# BLDC_driver_board.net
KiCad netlist of a schematic drawn in EAGLE
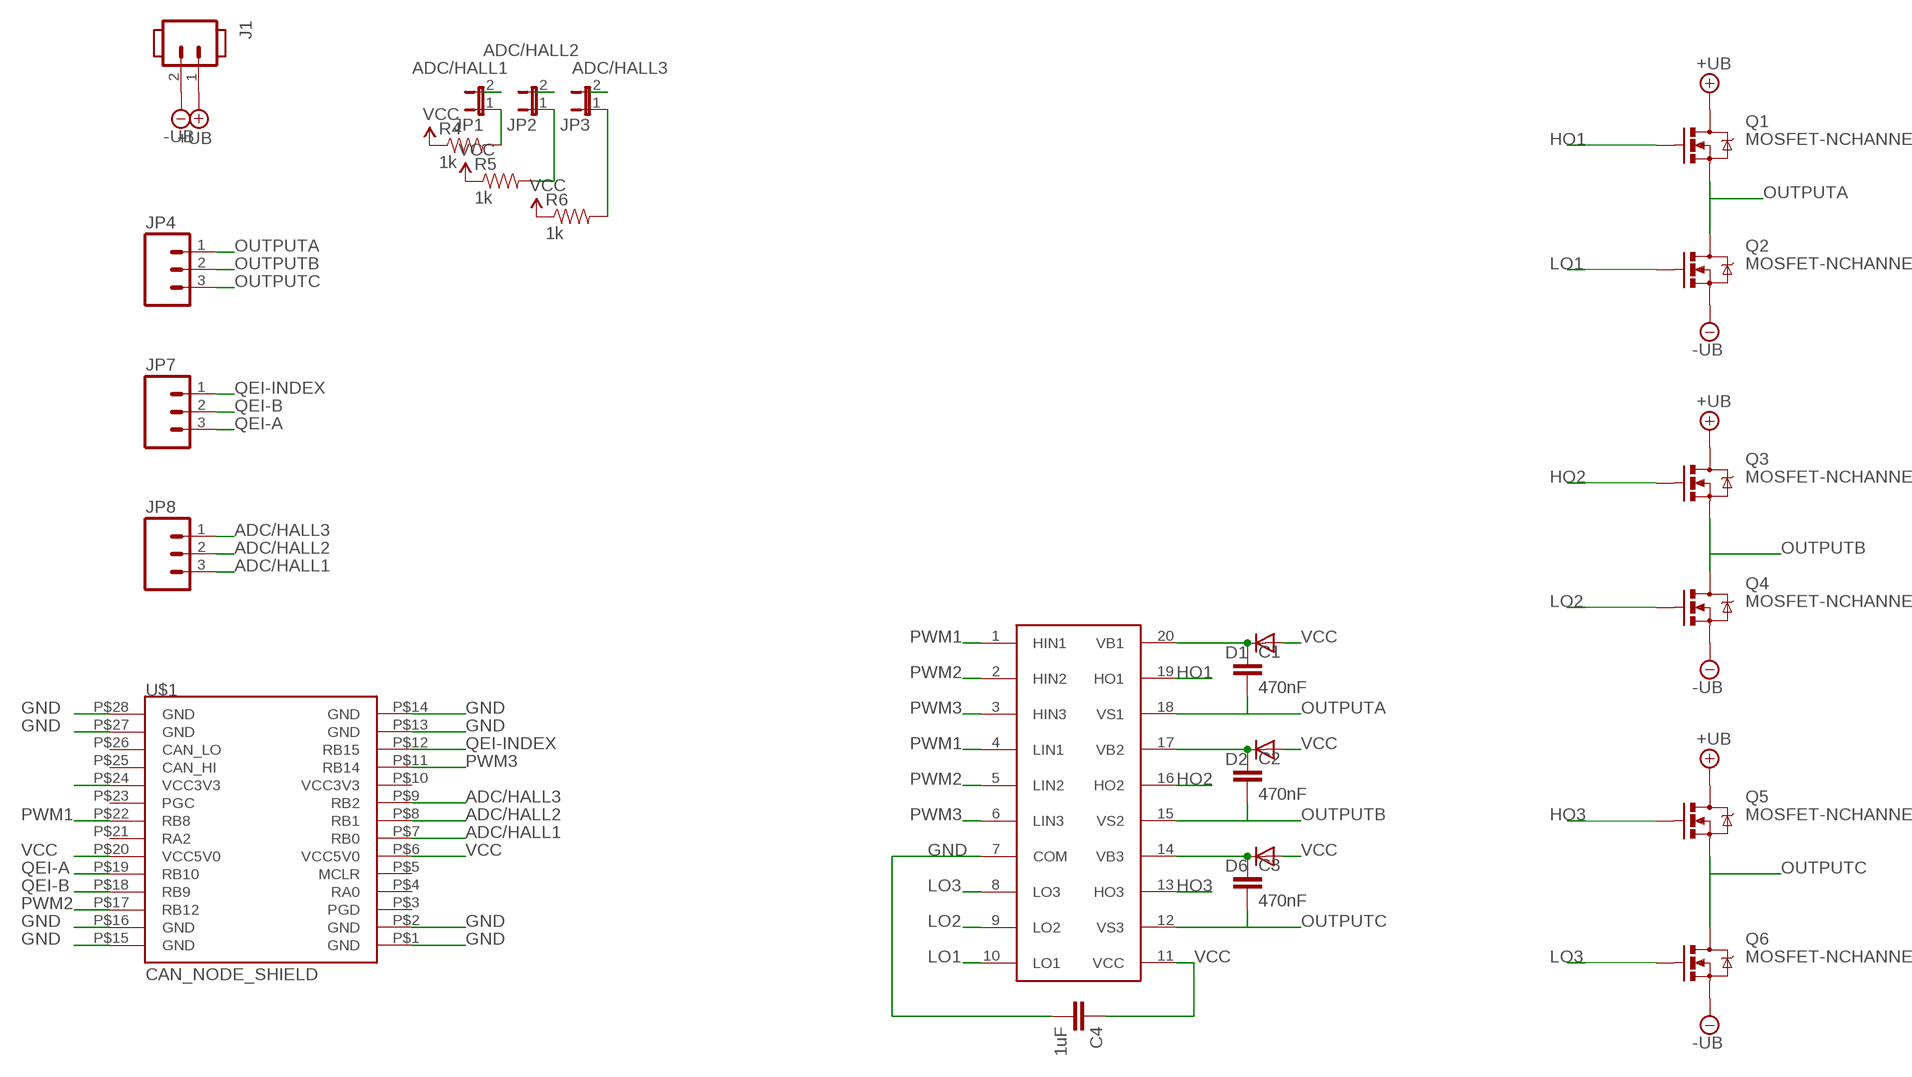
[diagram p0: schematic, sheet 1]

(export (version "E")
  (design (tool "Eeschema 10.0.6"))
  (components
    (comp (ref "C1")
      (value "470nF")
      (footprint "eagle-import:1206")
      (libsource (lib "eagle-import") (part "CAP1206"))
    )
    (comp (ref "C2")
      (value "470nF")
      (footprint "eagle-import:1206")
      (libsource (lib "eagle-import") (part "CAP1206"))
    )
    (comp (ref "C3")
      (value "470nF")
      (footprint "eagle-import:1206")
      (libsource (lib "eagle-import") (part "CAP1206"))
    )
    (comp (ref "C4")
      (value "1uF")
      (footprint "eagle-import:1206")
      (libsource (lib "eagle-import") (part "CAP1206"))
    )
    (comp (ref "D1")
      (value "DIODEHV")
      (footprint "eagle-import:DIODE-HV")
      (libsource (lib "eagle-import") (part "DIODEHV"))
    )
    (comp (ref "D2")
      (value "DIODEHV")
      (footprint "eagle-import:DIODE-HV")
      (libsource (lib "eagle-import") (part "DIODEHV"))
    )
    (comp (ref "D6")
      (value "DIODEHV")
      (footprint "eagle-import:DIODE-HV")
      (libsource (lib "eagle-import") (part "DIODEHV"))
    )
    (comp (ref "J1")
      (value "SCREWTERM02")
      (footprint "eagle-import:SCREW_TERMINAL-5.08MM-2")
      (libsource (lib "eagle-import") (part "SCREWTERM02"))
    )
    (comp (ref "JP1")
      (value "JP1E")
      (footprint "eagle-import:JP1")
      (libsource (lib "eagle-import") (part "JP1E"))
    )
    (comp (ref "JP2")
      (value "JP1E")
      (footprint "eagle-import:JP1")
      (libsource (lib "eagle-import") (part "JP1E"))
    )
    (comp (ref "JP3")
      (value "JP1E")
      (footprint "eagle-import:JP1")
      (libsource (lib "eagle-import") (part "JP1E"))
    )
    (comp (ref "JP4")
      (value "M03SCREW_LOCK")
      (footprint "eagle-import:SCREWTERMINAL-3.5MM-3_LOCK.007S")
      (libsource (lib "eagle-import") (part "M03SCREW_LOCK"))
    )
    (comp (ref "JP7")
      (value "M03LOCK_NO_SILK")
      (footprint "eagle-import:1X03_LOCK_NO_SILK")
      (libsource (lib "eagle-import") (part "M03LOCK_NO_SILK"))
    )
    (comp (ref "JP8")
      (value "M03LOCK_NO_SILK")
      (footprint "eagle-import:1X03_LOCK_NO_SILK")
      (libsource (lib "eagle-import") (part "M03LOCK_NO_SILK"))
    )
    (comp (ref "Q1")
      (value "MOSFET-NCHANNEL")
      (footprint "eagle-import:DPAK-VIA")
      (libsource (lib "eagle-import") (part "MOSFET-NCHANNEL"))
    )
    (comp (ref "Q2")
      (value "MOSFET-NCHANNEL")
      (footprint "eagle-import:DPAK-VIA")
      (libsource (lib "eagle-import") (part "MOSFET-NCHANNEL"))
    )
    (comp (ref "Q3")
      (value "MOSFET-NCHANNEL")
      (footprint "eagle-import:DPAK-VIA")
      (libsource (lib "eagle-import") (part "MOSFET-NCHANNEL"))
    )
    (comp (ref "Q4")
      (value "MOSFET-NCHANNEL")
      (footprint "eagle-import:DPAK-VIA")
      (libsource (lib "eagle-import") (part "MOSFET-NCHANNEL"))
    )
    (comp (ref "Q5")
      (value "MOSFET-NCHANNEL")
      (footprint "eagle-import:DPAK-VIA")
      (libsource (lib "eagle-import") (part "MOSFET-NCHANNEL"))
    )
    (comp (ref "Q6")
      (value "MOSFET-NCHANNEL")
      (footprint "eagle-import:DPAK-VIA")
      (libsource (lib "eagle-import") (part "MOSFET-NCHANNEL"))
    )
    (comp (ref "R4")
      (value "1k")
      (footprint "eagle-import:1206")
      (libsource (lib "eagle-import") (part "RESISTOR1206"))
    )
    (comp (ref "R5")
      (value "1k")
      (footprint "eagle-import:1206")
      (libsource (lib "eagle-import") (part "RESISTOR1206"))
    )
    (comp (ref "R6")
      (value "1k")
      (footprint "eagle-import:1206")
      (libsource (lib "eagle-import") (part "RESISTOR1206"))
    )
    (comp (ref "U$1")
      (value "CAN_NODE_SHIELD")
      (footprint "eagle-import:CAN_NODE_SHIELD")
      (libsource (lib "eagle-import") (part "CAN_NODE_SHIELD"))
    )
    (comp (ref "U2")
      (value "AUIRS2334S")
      (footprint "eagle-import:SO20W")
      (libsource (lib "eagle-import") (part "AUIRS2334S"))
    )
  )
  (nets
    (net (code "1") (name "+UB") (class "Default")
      (node (ref "J1") (pin "1") (pinfunction "1_1") (pintype "passive"))
      (node (ref "Q1") (pin "4") (pinfunction "D_4") (pintype "passive"))
      (node (ref "Q1") (pin "4@1") (pinfunction "D_4@1") (pintype "passive"))
      (node (ref "Q1") (pin "P$2") (pinfunction "D_P$2") (pintype "passive"))
      (node (ref "Q1") (pin "P$3") (pinfunction "D_P$3") (pintype "passive"))
      (node (ref "Q1") (pin "P$4") (pinfunction "D_P$4") (pintype "passive"))
      (node (ref "Q1") (pin "P$5") (pinfunction "D_P$5") (pintype "passive"))
      (node (ref "Q1") (pin "P$6") (pinfunction "D_P$6") (pintype "passive"))
      (node (ref "Q1") (pin "P$7") (pinfunction "D_P$7") (pintype "passive"))
      (node (ref "Q1") (pin "P$8") (pinfunction "D_P$8") (pintype "passive"))
      (node (ref "Q1") (pin "P$9") (pinfunction "D_P$9") (pintype "passive"))
      (node (ref "Q3") (pin "4") (pinfunction "D_4") (pintype "passive"))
      (node (ref "Q3") (pin "4@1") (pinfunction "D_4@1") (pintype "passive"))
      (node (ref "Q3") (pin "P$2") (pinfunction "D_P$2") (pintype "passive"))
      (node (ref "Q3") (pin "P$3") (pinfunction "D_P$3") (pintype "passive"))
      (node (ref "Q3") (pin "P$4") (pinfunction "D_P$4") (pintype "passive"))
      (node (ref "Q3") (pin "P$5") (pinfunction "D_P$5") (pintype "passive"))
      (node (ref "Q3") (pin "P$6") (pinfunction "D_P$6") (pintype "passive"))
      (node (ref "Q3") (pin "P$7") (pinfunction "D_P$7") (pintype "passive"))
      (node (ref "Q3") (pin "P$8") (pinfunction "D_P$8") (pintype "passive"))
      (node (ref "Q3") (pin "P$9") (pinfunction "D_P$9") (pintype "passive"))
      (node (ref "Q5") (pin "4") (pinfunction "D_4") (pintype "passive"))
      (node (ref "Q5") (pin "4@1") (pinfunction "D_4@1") (pintype "passive"))
      (node (ref "Q5") (pin "P$2") (pinfunction "D_P$2") (pintype "passive"))
      (node (ref "Q5") (pin "P$3") (pinfunction "D_P$3") (pintype "passive"))
      (node (ref "Q5") (pin "P$4") (pinfunction "D_P$4") (pintype "passive"))
      (node (ref "Q5") (pin "P$5") (pinfunction "D_P$5") (pintype "passive"))
      (node (ref "Q5") (pin "P$6") (pinfunction "D_P$6") (pintype "passive"))
      (node (ref "Q5") (pin "P$7") (pinfunction "D_P$7") (pintype "passive"))
      (node (ref "Q5") (pin "P$8") (pinfunction "D_P$8") (pintype "passive"))
      (node (ref "Q5") (pin "P$9") (pinfunction "D_P$9") (pintype "passive"))
    )
    (net (code "2") (name "-UB") (class "Default")
      (node (ref "J1") (pin "2") (pinfunction "2_2") (pintype "passive"))
      (node (ref "Q2") (pin "3") (pinfunction "S_3") (pintype "passive"))
      (node (ref "Q4") (pin "3") (pinfunction "S_3") (pintype "passive"))
      (node (ref "Q6") (pin "3") (pinfunction "S_3") (pintype "passive"))
    )
    (net (code "3") (name "/ADC{slash}HALL1") (class "Default")
      (node (ref "JP1") (pin "2") (pinfunction "2_2") (pintype "passive"))
      (node (ref "JP8") (pin "3") (pinfunction "3_3") (pintype "passive"))
      (node (ref "U$1") (pin "P$7") (pinfunction "RB0_P$7") (pintype "bidirectional"))
    )
    (net (code "4") (name "/ADC{slash}HALL2") (class "Default")
      (node (ref "JP2") (pin "2") (pinfunction "2_2") (pintype "passive"))
      (node (ref "JP8") (pin "2") (pinfunction "2_2") (pintype "passive"))
      (node (ref "U$1") (pin "P$8") (pinfunction "RB1_P$8") (pintype "bidirectional"))
    )
    (net (code "5") (name "/ADC{slash}HALL3") (class "Default")
      (node (ref "JP3") (pin "2") (pinfunction "2_2") (pintype "passive"))
      (node (ref "JP8") (pin "1") (pinfunction "1_1") (pintype "passive"))
      (node (ref "U$1") (pin "P$9") (pinfunction "RB2_P$9") (pintype "bidirectional"))
    )
    (net (code "6") (name "/GND") (class "Default")
      (node (ref "C4") (pin "2") (pinfunction "2_2") (pintype "passive"))
      (node (ref "U$1") (pin "P$1") (pinfunction "GND_P$1") (pintype "bidirectional"))
      (node (ref "U$1") (pin "P$13") (pinfunction "GND_P$13") (pintype "bidirectional"))
      (node (ref "U$1") (pin "P$14") (pinfunction "GND_P$14") (pintype "bidirectional"))
      (node (ref "U$1") (pin "P$15") (pinfunction "GND_P$15") (pintype "bidirectional"))
      (node (ref "U$1") (pin "P$16") (pinfunction "GND_P$16") (pintype "bidirectional"))
      (node (ref "U$1") (pin "P$2") (pinfunction "GND_P$2") (pintype "bidirectional"))
      (node (ref "U$1") (pin "P$27") (pinfunction "GND_P$27") (pintype "bidirectional"))
      (node (ref "U$1") (pin "P$28") (pinfunction "GND_P$28") (pintype "bidirectional"))
      (node (ref "U2") (pin "7") (pinfunction "COM_7") (pintype "bidirectional"))
    )
    (net (code "7") (name "/HO1") (class "Default")
      (node (ref "Q1") (pin "1") (pinfunction "G_1") (pintype "passive"))
      (node (ref "U2") (pin "19") (pinfunction "HO1_19") (pintype "bidirectional"))
    )
    (net (code "8") (name "/HO2") (class "Default")
      (node (ref "Q3") (pin "1") (pinfunction "G_1") (pintype "passive"))
      (node (ref "U2") (pin "16") (pinfunction "HO2_16") (pintype "bidirectional"))
    )
    (net (code "9") (name "/HO3") (class "Default")
      (node (ref "Q5") (pin "1") (pinfunction "G_1") (pintype "passive"))
      (node (ref "U2") (pin "13") (pinfunction "HO3_13") (pintype "bidirectional"))
    )
    (net (code "10") (name "/LO1") (class "Default")
      (node (ref "Q2") (pin "1") (pinfunction "G_1") (pintype "passive"))
      (node (ref "U2") (pin "10") (pinfunction "LO1_10") (pintype "bidirectional"))
    )
    (net (code "11") (name "/LO2") (class "Default")
      (node (ref "Q4") (pin "1") (pinfunction "G_1") (pintype "passive"))
      (node (ref "U2") (pin "9") (pinfunction "LO2_9") (pintype "bidirectional"))
    )
    (net (code "12") (name "/LO3") (class "Default")
      (node (ref "Q6") (pin "1") (pinfunction "G_1") (pintype "passive"))
      (node (ref "U2") (pin "8") (pinfunction "LO3_8") (pintype "bidirectional"))
    )
    (net (code "13") (name "/OUTPUTA") (class "Default")
      (node (ref "C1") (pin "2") (pinfunction "2_2") (pintype "passive"))
      (node (ref "JP4") (pin "1") (pinfunction "1_1") (pintype "passive"))
      (node (ref "Q1") (pin "3") (pinfunction "S_3") (pintype "passive"))
      (node (ref "Q2") (pin "4") (pinfunction "D_4") (pintype "passive"))
      (node (ref "Q2") (pin "4@1") (pinfunction "D_4@1") (pintype "passive"))
      (node (ref "Q2") (pin "P$2") (pinfunction "D_P$2") (pintype "passive"))
      (node (ref "Q2") (pin "P$3") (pinfunction "D_P$3") (pintype "passive"))
      (node (ref "Q2") (pin "P$4") (pinfunction "D_P$4") (pintype "passive"))
      (node (ref "Q2") (pin "P$5") (pinfunction "D_P$5") (pintype "passive"))
      (node (ref "Q2") (pin "P$6") (pinfunction "D_P$6") (pintype "passive"))
      (node (ref "Q2") (pin "P$7") (pinfunction "D_P$7") (pintype "passive"))
      (node (ref "Q2") (pin "P$8") (pinfunction "D_P$8") (pintype "passive"))
      (node (ref "Q2") (pin "P$9") (pinfunction "D_P$9") (pintype "passive"))
      (node (ref "U2") (pin "18") (pinfunction "VS1_18") (pintype "bidirectional"))
    )
    (net (code "14") (name "/OUTPUTB") (class "Default")
      (node (ref "C2") (pin "2") (pinfunction "2_2") (pintype "passive"))
      (node (ref "JP4") (pin "2") (pinfunction "2_2") (pintype "passive"))
      (node (ref "Q3") (pin "3") (pinfunction "S_3") (pintype "passive"))
      (node (ref "Q4") (pin "4") (pinfunction "D_4") (pintype "passive"))
      (node (ref "Q4") (pin "4@1") (pinfunction "D_4@1") (pintype "passive"))
      (node (ref "Q4") (pin "P$2") (pinfunction "D_P$2") (pintype "passive"))
      (node (ref "Q4") (pin "P$3") (pinfunction "D_P$3") (pintype "passive"))
      (node (ref "Q4") (pin "P$4") (pinfunction "D_P$4") (pintype "passive"))
      (node (ref "Q4") (pin "P$5") (pinfunction "D_P$5") (pintype "passive"))
      (node (ref "Q4") (pin "P$6") (pinfunction "D_P$6") (pintype "passive"))
      (node (ref "Q4") (pin "P$7") (pinfunction "D_P$7") (pintype "passive"))
      (node (ref "Q4") (pin "P$8") (pinfunction "D_P$8") (pintype "passive"))
      (node (ref "Q4") (pin "P$9") (pinfunction "D_P$9") (pintype "passive"))
      (node (ref "U2") (pin "15") (pinfunction "VS2_15") (pintype "bidirectional"))
    )
    (net (code "15") (name "/OUTPUTC") (class "Default")
      (node (ref "C3") (pin "2") (pinfunction "2_2") (pintype "passive"))
      (node (ref "JP4") (pin "3") (pinfunction "3_3") (pintype "passive"))
      (node (ref "Q5") (pin "3") (pinfunction "S_3") (pintype "passive"))
      (node (ref "Q6") (pin "4") (pinfunction "D_4") (pintype "passive"))
      (node (ref "Q6") (pin "4@1") (pinfunction "D_4@1") (pintype "passive"))
      (node (ref "Q6") (pin "P$2") (pinfunction "D_P$2") (pintype "passive"))
      (node (ref "Q6") (pin "P$3") (pinfunction "D_P$3") (pintype "passive"))
      (node (ref "Q6") (pin "P$4") (pinfunction "D_P$4") (pintype "passive"))
      (node (ref "Q6") (pin "P$5") (pinfunction "D_P$5") (pintype "passive"))
      (node (ref "Q6") (pin "P$6") (pinfunction "D_P$6") (pintype "passive"))
      (node (ref "Q6") (pin "P$7") (pinfunction "D_P$7") (pintype "passive"))
      (node (ref "Q6") (pin "P$8") (pinfunction "D_P$8") (pintype "passive"))
      (node (ref "Q6") (pin "P$9") (pinfunction "D_P$9") (pintype "passive"))
      (node (ref "U2") (pin "12") (pinfunction "VS3_12") (pintype "bidirectional"))
    )
    (net (code "16") (name "/PWM1") (class "Default")
      (node (ref "U$1") (pin "P$22") (pinfunction "RB8_P$22") (pintype "bidirectional"))
      (node (ref "U2") (pin "1") (pinfunction "HIN1_1") (pintype "bidirectional"))
      (node (ref "U2") (pin "4") (pinfunction "LIN1_4") (pintype "bidirectional"))
    )
    (net (code "17") (name "/PWM2") (class "Default")
      (node (ref "U$1") (pin "P$17") (pinfunction "RB12_P$17") (pintype "bidirectional"))
      (node (ref "U2") (pin "2") (pinfunction "HIN2_2") (pintype "bidirectional"))
      (node (ref "U2") (pin "5") (pinfunction "LIN2_5") (pintype "bidirectional"))
    )
    (net (code "18") (name "/PWM3") (class "Default")
      (node (ref "U$1") (pin "P$11") (pinfunction "RB14_P$11") (pintype "bidirectional"))
      (node (ref "U2") (pin "3") (pinfunction "HIN3_3") (pintype "bidirectional"))
      (node (ref "U2") (pin "6") (pinfunction "LIN3_6") (pintype "bidirectional"))
    )
    (net (code "19") (name "/QEI-A") (class "Default")
      (node (ref "JP7") (pin "3") (pinfunction "3_3") (pintype "passive"))
      (node (ref "U$1") (pin "P$19") (pinfunction "RB10_P$19") (pintype "bidirectional"))
    )
    (net (code "20") (name "/QEI-B") (class "Default")
      (node (ref "JP7") (pin "2") (pinfunction "2_2") (pintype "passive"))
      (node (ref "U$1") (pin "P$18") (pinfunction "RB9_P$18") (pintype "bidirectional"))
    )
    (net (code "21") (name "/QEI-INDEX") (class "Default")
      (node (ref "JP7") (pin "1") (pinfunction "1_1") (pintype "passive"))
      (node (ref "U$1") (pin "P$12") (pinfunction "RB15_P$12") (pintype "bidirectional"))
    )
    (net (code "22") (name "Net-(JP1-Pad1)") (class "Default")
      (node (ref "JP1") (pin "1") (pinfunction "1_1") (pintype "passive"))
      (node (ref "R4") (pin "2") (pinfunction "2_2") (pintype "passive"))
    )
    (net (code "23") (name "Net-(JP2-Pad1)") (class "Default")
      (node (ref "JP2") (pin "1") (pinfunction "1_1") (pintype "passive"))
      (node (ref "R5") (pin "2") (pinfunction "2_2") (pintype "passive"))
    )
    (net (code "24") (name "Net-(JP3-Pad1)") (class "Default")
      (node (ref "JP3") (pin "1") (pinfunction "1_1") (pintype "passive"))
      (node (ref "R6") (pin "2") (pinfunction "2_2") (pintype "passive"))
    )
    (net (code "25") (name "Net-(U2-VB1)") (class "Default")
      (node (ref "C1") (pin "1") (pinfunction "1_1") (pintype "passive"))
      (node (ref "D1") (pin "C") (pinfunction "C_C") (pintype "passive"))
      (node (ref "U2") (pin "20") (pinfunction "VB1_20") (pintype "bidirectional"))
    )
    (net (code "26") (name "Net-(U2-VB2)") (class "Default")
      (node (ref "C2") (pin "1") (pinfunction "1_1") (pintype "passive"))
      (node (ref "D2") (pin "C") (pinfunction "C_C") (pintype "passive"))
      (node (ref "U2") (pin "17") (pinfunction "VB2_17") (pintype "bidirectional"))
    )
    (net (code "27") (name "Net-(U2-VB3)") (class "Default")
      (node (ref "C3") (pin "1") (pinfunction "1_1") (pintype "passive"))
      (node (ref "D6") (pin "C") (pinfunction "C_C") (pintype "passive"))
      (node (ref "U2") (pin "14") (pinfunction "VB3_14") (pintype "bidirectional"))
    )
    (net (code "28") (name "VCC") (class "Default")
      (node (ref "C4") (pin "1") (pinfunction "1_1") (pintype "passive"))
      (node (ref "D1") (pin "A") (pinfunction "A_A") (pintype "passive"))
      (node (ref "D2") (pin "A") (pinfunction "A_A") (pintype "passive"))
      (node (ref "D6") (pin "A") (pinfunction "A_A") (pintype "passive"))
      (node (ref "R4") (pin "1") (pinfunction "1_1") (pintype "passive"))
      (node (ref "R5") (pin "1") (pinfunction "1_1") (pintype "passive"))
      (node (ref "R6") (pin "1") (pinfunction "1_1") (pintype "passive"))
      (node (ref "U$1") (pin "P$20") (pinfunction "VCC5V0_P$20") (pintype "bidirectional"))
      (node (ref "U$1") (pin "P$6") (pinfunction "VCC5V0_P$6") (pintype "bidirectional"))
      (node (ref "U2") (pin "11") (pinfunction "VCC_11") (pintype "bidirectional"))
    )
    (net (code "29") (name "unconnected-(U$1-CAN_HI-PadP$25)") (class "Default")
      (node (ref "U$1") (pin "P$25") (pinfunction "CAN_HI_P$25") (pintype "bidirectional"))
    )
    (net (code "30") (name "unconnected-(U$1-CAN_LO-PadP$26)") (class "Default")
      (node (ref "U$1") (pin "P$26") (pinfunction "CAN_LO_P$26") (pintype "bidirectional"))
    )
    (net (code "31") (name "unconnected-(U$1-MCLR-PadP$5)") (class "Default")
      (node (ref "U$1") (pin "P$5") (pinfunction "MCLR_P$5") (pintype "bidirectional"))
    )
    (net (code "32") (name "unconnected-(U$1-PGC-PadP$23)") (class "Default")
      (node (ref "U$1") (pin "P$23") (pinfunction "PGC_P$23") (pintype "bidirectional"))
    )
    (net (code "33") (name "unconnected-(U$1-PGD-PadP$3)") (class "Default")
      (node (ref "U$1") (pin "P$3") (pinfunction "PGD_P$3") (pintype "bidirectional"))
    )
    (net (code "34") (name "unconnected-(U$1-RA0-PadP$4)") (class "Default")
      (node (ref "U$1") (pin "P$4") (pinfunction "RA0_P$4") (pintype "bidirectional"))
    )
    (net (code "35") (name "unconnected-(U$1-RA2-PadP$21)") (class "Default")
      (node (ref "U$1") (pin "P$21") (pinfunction "RA2_P$21") (pintype "bidirectional"))
    )
    (net (code "36") (name "unconnected-(U$1-VCC3V3-PadP$10)") (class "Default")
      (node (ref "U$1") (pin "P$10") (pinfunction "VCC3V3_P$10") (pintype "bidirectional"))
    )
    (net (code "37") (name "unconnected-(U$1-VCC3V3-PadP$24)") (class "Default")
      (node (ref "U$1") (pin "P$24") (pinfunction "VCC3V3_P$24") (pintype "bidirectional"))
    )
  )
)
